# 1S__tp4054.net
KiCad netlist of a schematic drawn in Altium Designer
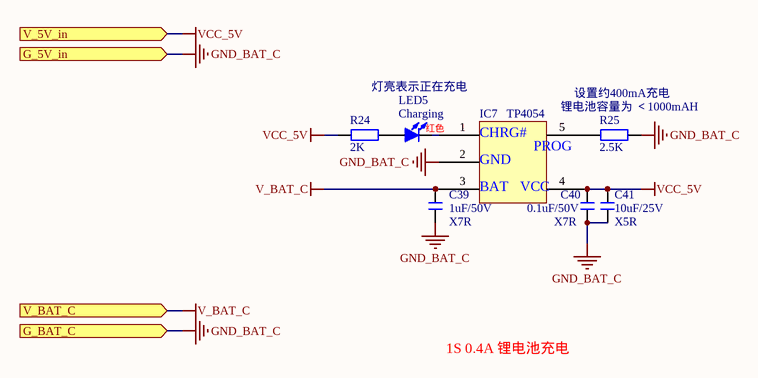
[diagram p0: 1S锂电池充电_tp4054.SchDoc]

(export (version "E")
  (design (tool "Eeschema 10.0.6"))
  (components
    (comp (ref "C39")
      (value "1uF/50V")
      (footprint "C 0603_L")
      (description "无极性贴片电容 X7R")
      (fields (field (name "BOM名称") "X7R"))
      (libsource (lib "Foundation_temp") (part "C X7R"))
    )
    (comp (ref "C40")
      (value "0.1uF/50V")
      (footprint "C 0402_L")
      (description "无极性贴片电容 X7R")
      (fields (field (name "BOM名称") "X7R"))
      (libsource (lib "Foundation_temp") (part "C X7R"))
    )
    (comp (ref "C41")
      (value "10uF/25V")
      (footprint "C 0603_L")
      (description "无极性贴片电容 X5R")
      (fields (field (name "BOM名称") "X5R"))
      (libsource (lib "Foundation_temp") (part "C X5R"))
    )
    (comp (ref "IC7")
      (value "TP4054")
      (footprint "SOT23-5N")
      (description "1S锂电充电")
      (libsource (lib "IC_temp") (part "5"))
    )
    (comp (ref "LED5")
      (value "Charging")
      (footprint "LED 0805R")
      (description "红色 贴片LED")
      (fields (field (name "版权归属") "源创客"))
      (libsource (lib "9.1   - LED") (part "LED-SMD"))
    )
    (comp (ref "R24")
      (value "2K")
      (footprint "R 0402_L")
      (description "贴片电阻 E-96 1%")
      (libsource (lib "Foundation_temp") (part "R"))
    )
    (comp (ref "R25")
      (value "2.5K")
      (footprint "R 0402_L")
      (description "贴片电阻 E-96 1%")
      (libsource (lib "Foundation_temp") (part "R"))
    )
  )
  (nets
    (net (code "1") (name "GND_BAT_C") (class "Default")
      (node (ref "C39") (pin "1") (pinfunction "1_1") (pintype "passive"))
      (node (ref "C40") (pin "2") (pinfunction "2_2") (pintype "passive"))
      (node (ref "C41") (pin "1") (pinfunction "1_1") (pintype "passive"))
      (node (ref "IC7") (pin "2") (pinfunction "2_2") (pintype "passive"))
      (node (ref "R25") (pin "2") (pinfunction "2_2") (pintype "passive"))
    )
    (net (code "2") (name "Net-(IC7-Pad5)") (class "Default")
      (node (ref "IC7") (pin "5") (pinfunction "5_5") (pintype "passive"))
      (node (ref "R25") (pin "1") (pinfunction "1_1") (pintype "passive"))
    )
    (net (code "3") (name "Net-(LED5-A)") (class "Default")
      (node (ref "LED5") (pin "1") (pinfunction "A_1") (pintype "passive"))
      (node (ref "R24") (pin "1") (pinfunction "1_1") (pintype "passive"))
    )
    (net (code "4") (name "Net-(LED5-K)") (class "Default")
      (node (ref "IC7") (pin "1") (pinfunction "1_1") (pintype "passive"))
      (node (ref "LED5") (pin "2") (pinfunction "K_2") (pintype "passive"))
    )
    (net (code "5") (name "VCC_5V") (class "Default")
      (node (ref "C40") (pin "1") (pinfunction "1_1") (pintype "passive"))
      (node (ref "C41") (pin "2") (pinfunction "2_2") (pintype "passive"))
      (node (ref "IC7") (pin "4") (pinfunction "4_4") (pintype "passive"))
      (node (ref "R24") (pin "2") (pinfunction "2_2") (pintype "passive"))
    )
    (net (code "6") (name "V_BAT_C") (class "Default")
      (node (ref "C39") (pin "2") (pinfunction "2_2") (pintype "passive"))
      (node (ref "IC7") (pin "3") (pinfunction "3_3") (pintype "passive"))
    )
  )
)
